# MercurialSDR_FPGA_P_P.net
KiCad netlist of a schematic drawn in Altium Designer
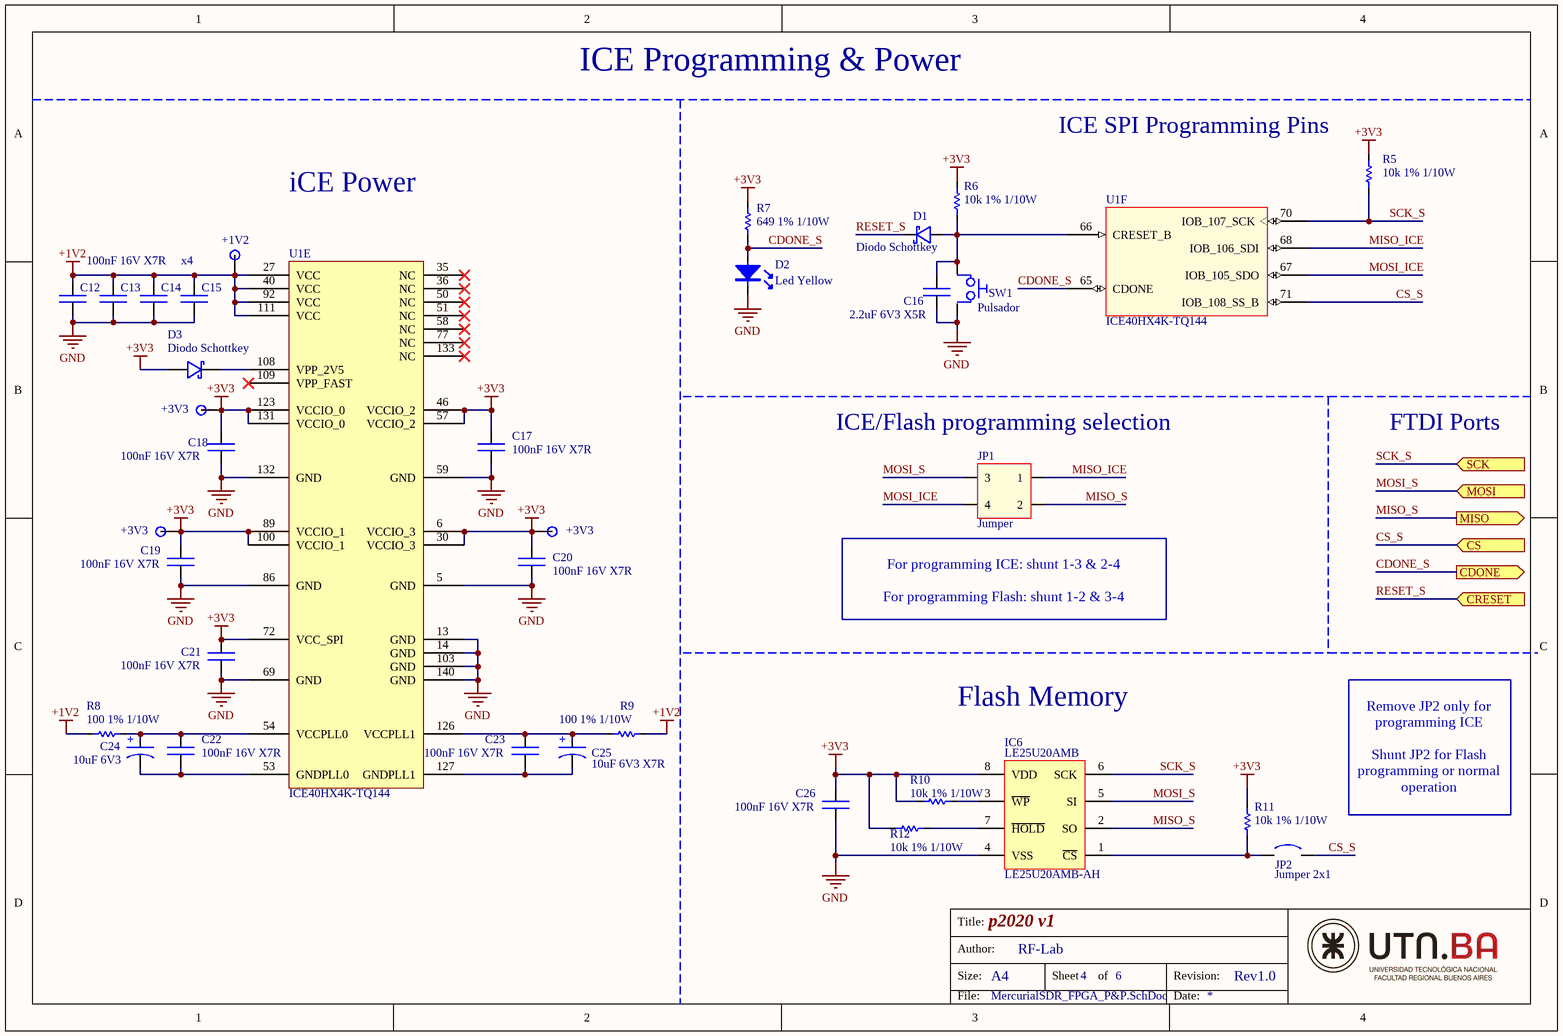
[diagram p0: MercurialSDR_FPGA_P&P.SchDoc]

(export (version "E")
  (design (tool "Eeschema 10.0.6"))
  (components
    (comp (ref "C12")
      (value "100nF 16V X7R - CL10B104KO8NNNC")
      (footprint "CAP_0603")
      (description "Capacitor no polarizado")
      (libsource (lib "MercurialSDR") (part "Cap"))
    )
    (comp (ref "C13")
      (value "100nF 16V X7R - CL10B104KO8NNNC")
      (footprint "CAP_0603")
      (description "Capacitor no polarizado")
      (fields (field (name "PART NUMBER") "CL10B104KO8NNNC"))
      (libsource (lib "MercurialSDR") (part "Cap"))
    )
    (comp (ref "C14")
      (value "100nF 16V X7R - CL10B104KO8NNNC")
      (footprint "CAP_0603")
      (description "Capacitor no polarizado")
      (fields (field (name "PART NUMBER") "CL10B104KO8NNNC"))
      (libsource (lib "MercurialSDR") (part "Cap"))
    )
    (comp (ref "C15")
      (value "100nF 16V X7R")
      (footprint "CAP_0603")
      (description "Capacitor no polarizado")
      (fields (field (name "Comment") "100nF 16V X7R - CL10B104KO8NNNC"))
      (libsource (lib "MercurialSDR") (part "Cap"))
    )
    (comp (ref "C16")
      (value "2.2uF 6V3 X5R")
      (footprint "CAP_0603")
      (description "Capacitor no polarizado")
      (fields (field (name "Comment") "2.2uF 6V3 X5R - CL10A225KQ8NNNC"))
      (libsource (lib "MercurialSDR") (part "Cap"))
    )
    (comp (ref "C17")
      (value "100nF 16V X7R")
      (footprint "CAP_0603")
      (description "Capacitor no polarizado")
      (fields (field (name "Comment") "100nF 16V X7R - CL10B104KO8NNNC"))
      (libsource (lib "MercurialSDR") (part "Cap"))
    )
    (comp (ref "C18")
      (value "100nF 16V X7R")
      (footprint "CAP_0603")
      (description "Capacitor no polarizado")
      (fields (field (name "Comment") "100nF 16V X7R - CL10B104KO8NNNC"))
      (libsource (lib "MercurialSDR") (part "Cap"))
    )
    (comp (ref "C19")
      (value "100nF 16V X7R")
      (footprint "CAP_0603")
      (description "Capacitor no polarizado")
      (fields (field (name "Comment") "100nF 16V X7R - CL10B104KO8NNNC"))
      (libsource (lib "MercurialSDR") (part "Cap"))
    )
    (comp (ref "C20")
      (value "100nF 16V X7R")
      (footprint "CAP_0603")
      (description "Capacitor no polarizado")
      (fields (field (name "Comment") "100nF 16V X7R - CL10B104KO8NNNC"))
      (libsource (lib "MercurialSDR") (part "Cap"))
    )
    (comp (ref "C21")
      (value "100nF 16V X7R")
      (footprint "CAP_0603")
      (description "Capacitor no polarizado")
      (fields (field (name "Comment") "100nF 16V X7R - CL10B104KO8NNNC"))
      (libsource (lib "MercurialSDR") (part "Cap"))
    )
    (comp (ref "C22")
      (value "100nF 16V X7R")
      (footprint "CAP_0603")
      (description "Capacitor no polarizado")
      (fields (field (name "Comment") "100nF 16V X7R - CL10B104KO8NNNC"))
      (libsource (lib "MercurialSDR") (part "Cap"))
    )
    (comp (ref "C23")
      (value "100nF 16V X7R")
      (footprint "CAP_0603")
      (description "Capacitor no polarizado")
      (fields (field (name "Comment") "100nF 16V X7R - CL10B104KO8NNNC"))
      (libsource (lib "MercurialSDR") (part "Cap"))
    )
    (comp (ref "C24")
      (value "10uF 6V3")
      (footprint "CAP_TANT_1206")
      (description "Capacitor polarizado")
      (fields (field (name "Comment") "10uF 6V3 - TAJA106K006RNJ"))
      (libsource (lib "MercurialSDR") (part "Cap Pol"))
    )
    (comp (ref "C25")
      (value "10uF 6V3 X7R")
      (footprint "CAP_TANT_1206")
      (description "Capacitor polarizado")
      (fields (field (name "Comment") "10uF 6V3 X7R- TAJA106K006RNJ"))
      (libsource (lib "MercurialSDR") (part "Cap Pol"))
    )
    (comp (ref "C26")
      (value "100nF 16V X7R")
      (footprint "CAP_0603")
      (description "Capacitor no polarizado")
      (fields (field (name "Comment") "100nF 16V X7R - CL10B104KO8NNNC"))
      (libsource (lib "MercurialSDR") (part "Cap"))
    )
    (comp (ref "D1")
      (value "Diodo Schottkey")
      (footprint "SOD-523")
      (fields (field (name "Comment") "RB521S30T1G"))
      (libsource (lib "MercurialSDR") (part "Diodo_Schottky"))
    )
    (comp (ref "D2")
      (value "Led Yellow")
      (footprint "LED_0603")
      (description "Led")
      (fields (field (name "Comment") "LTST-C190KSKT"))
      (libsource (lib "MercurialSDR") (part "Led"))
    )
    (comp (ref "D3")
      (value "Diodo Schottkey")
      (footprint "SOD-323")
      (fields (field (name "PART NUMBER") "NSR0530HT1G"))
      (libsource (lib "") (part "Diodo_Schottky_1"))
    )
    (comp (ref "IC6")
      (value "LE25U20AMB")
      (footprint "SOIC-8")
      (description "Flash Memmory SPI (256Kx8)")
      (fields (field (name "PART NUMBER") "LE25U20AMB-AH"))
      (libsource (lib "MercurialSDR") (part "LE25U20AMB"))
    )
    (comp (ref "JP1")
      (value "Jumper")
      (footprint "Jumper 2x2")
      (description "Jumper 2x2")
      (libsource (lib "MercurialSDR") (part "Jumper 2x2"))
    )
    (comp (ref "JP2")
      (value "Jumper 2x1")
      (footprint "Jumper 2x1")
      (description "Jumper")
      (libsource (lib "MercurialSDR") (part "Jumper"))
    )
    (comp (ref "R5")
      (value "10k 1% 1/10W")
      (footprint "RES_0603")
      (description "Resistor")
      (fields (field (name "Comment") "10k 1% 1/10W - CR0603-FX-1002EAS"))
      (libsource (lib "MercurialSDR") (part "Res"))
    )
    (comp (ref "R6")
      (value "10k 1% 1/10W")
      (footprint "RES_0603")
      (description "Resistor")
      (fields (field (name "Comment") "10k 1% 1/10W - CR0603-FX-1002EAS"))
      (libsource (lib "MercurialSDR") (part "Res"))
    )
    (comp (ref "R7")
      (value "649 1% 1/10W")
      (footprint "RES_0603")
      (description "Resistor")
      (fields (field (name "Comment") "649 1% 1/10W - RC0603FR-07649RL"))
      (libsource (lib "MercurialSDR") (part "Res"))
    )
    (comp (ref "R8")
      (value "100 1% 1/10W")
      (footprint "RES_0603")
      (description "Resistor")
      (fields (field (name "Comment") "100 1% 1/10W - CR0603-FX-1000ELF"))
      (libsource (lib "MercurialSDR") (part "Res"))
    )
    (comp (ref "R9")
      (value "100 1% 1/10W")
      (footprint "RES_0603")
      (description "Resistor")
      (fields (field (name "POWER") "1/10W") (field (name "PART NUMBER") "CR0603-FX-1000ELF"))
      (libsource (lib "MercurialSDR") (part "Res"))
    )
    (comp (ref "R10")
      (value "10k 1% 1/10W")
      (footprint "RES_0603")
      (description "Resistor")
      (fields (field (name "Comment") "10k 1% 1/10W - CR0603-FX-1002EAS"))
      (libsource (lib "MercurialSDR") (part "Res"))
    )
    (comp (ref "R11")
      (value "10k 1% 1/10W")
      (footprint "RES_0603")
      (description "Resistor")
      (fields (field (name "Comment") "10k 1% 1/10W - CR0603-FX-1002EAS"))
      (libsource (lib "MercurialSDR") (part "Res"))
    )
    (comp (ref "R12")
      (value "10k 1% 1/10W")
      (footprint "RES_0603")
      (description "Resistor")
      (fields (field (name "Comment") "10k 1% 1/10W - CR0603-FX-1002EAS"))
      (libsource (lib "MercurialSDR") (part "Res"))
    )
    (comp (ref "SW1")
      (value "Pulsador")
      (footprint "SWITCH_6X6mm")
      (fields (field (name "Comment") "PTS645SM43SMTR92 LFS"))
      (libsource (lib "MercurialSDR") (part "Pulsador"))
    )
    (comp (ref "TP2")
      (value "Test Point")
      (footprint "TP_TH")
      (fields (field (name "TP NAME") "+1V2"))
      (libsource (lib "MercurialSDR") (part "Test Point"))
    )
    (comp (ref "TP3")
      (value "Test Point")
      (footprint "TP_TH")
      (fields (field (name "TP NAME") "+3V3"))
      (libsource (lib "MercurialSDR") (part "Test Point"))
    )
    (comp (ref "TP4")
      (value "Test Point")
      (footprint "TP_TH")
      (fields (field (name "TP NAME") "+3V3"))
      (libsource (lib "MercurialSDR") (part "Test Point"))
    )
    (comp (ref "TP5")
      (value "Test Point")
      (footprint "TP_TH")
      (fields (field (name "TP NAME") "+3V3"))
      (libsource (lib "MercurialSDR") (part "Test Point"))
    )
    (comp (ref "U1")
      (value "ICE40HX4K-TQ144")
      (footprint "LATC-TQFP-144_L")
      (description "iCE40 HX4K Series FPGA Family")
      (fields (field (name "MANUFACTURER") "Lattice Semiconductor"))
      (libsource (lib "MercurialSDR") (part "ICE40HX4K-TQ144"))
    )
  )
  (nets
    (net (code "1") (name "+1V2") (class "Default")
      (node (ref "C12") (pin "1") (pinfunction "1_1") (pintype "passive"))
      (node (ref "C13") (pin "1") (pinfunction "1_1") (pintype "passive"))
      (node (ref "C14") (pin "1") (pinfunction "1_1") (pintype "passive"))
      (node (ref "C15") (pin "1") (pinfunction "1_1") (pintype "passive"))
      (node (ref "R8") (pin "2") (pinfunction "2_2") (pintype "passive"))
      (node (ref "R9") (pin "1") (pinfunction "1_1") (pintype "passive"))
      (node (ref "TP2") (pin "1") (pinfunction "TP?_1") (pintype "passive"))
      (node (ref "U1") (pin "111") (pinfunction "VCC_111") (pintype "power_in"))
      (node (ref "U1") (pin "27") (pinfunction "VCC_27") (pintype "power_in"))
      (node (ref "U1") (pin "40") (pinfunction "VCC_40") (pintype "power_in"))
      (node (ref "U1") (pin "92") (pinfunction "VCC_92") (pintype "power_in"))
    )
    (net (code "2") (name "+3V3") (class "Default")
      (node (ref "C17") (pin "2") (pinfunction "2_2") (pintype "passive"))
      (node (ref "C18") (pin "2") (pinfunction "2_2") (pintype "passive"))
      (node (ref "C19") (pin "2") (pinfunction "2_2") (pintype "passive"))
      (node (ref "C20") (pin "2") (pinfunction "2_2") (pintype "passive"))
      (node (ref "C21") (pin "2") (pinfunction "2_2") (pintype "passive"))
      (node (ref "C26") (pin "2") (pinfunction "2_2") (pintype "passive"))
      (node (ref "D3") (pin "1") (pinfunction "A_1") (pintype "passive"))
      (node (ref "IC6") (pin "8") (pinfunction "VDD_8") (pintype "passive"))
      (node (ref "R10") (pin "1") (pinfunction "1_1") (pintype "passive"))
      (node (ref "R11") (pin "2") (pinfunction "2_2") (pintype "passive"))
      (node (ref "R12") (pin "1") (pinfunction "1_1") (pintype "passive"))
      (node (ref "R5") (pin "1") (pinfunction "1_1") (pintype "passive"))
      (node (ref "R6") (pin "1") (pinfunction "1_1") (pintype "passive"))
      (node (ref "R7") (pin "1") (pinfunction "1_1") (pintype "passive"))
      (node (ref "TP3") (pin "1") (pinfunction "TP?_1") (pintype "passive"))
      (node (ref "TP4") (pin "1") (pinfunction "TP?_1") (pintype "passive"))
      (node (ref "TP5") (pin "1") (pinfunction "TP?_1") (pintype "passive"))
      (node (ref "U1") (pin "100") (pinfunction "VCCIO_1_100") (pintype "power_in"))
      (node (ref "U1") (pin "123") (pinfunction "VCCIO_0_123") (pintype "power_in"))
      (node (ref "U1") (pin "131") (pinfunction "VCCIO_0_131") (pintype "power_in"))
      (node (ref "U1") (pin "30") (pinfunction "VCCIO_3_30") (pintype "power_in"))
      (node (ref "U1") (pin "46") (pinfunction "VCCIO_2_46") (pintype "power_in"))
      (node (ref "U1") (pin "57") (pinfunction "VCCIO_2_57") (pintype "power_in"))
      (node (ref "U1") (pin "6") (pinfunction "VCCIO_3_6") (pintype "power_in"))
      (node (ref "U1") (pin "72") (pinfunction "VCC_SPI_72") (pintype "power_in"))
      (node (ref "U1") (pin "89") (pinfunction "VCCIO_1_89") (pintype "power_in"))
    )
    (net (code "3") (name "/CDONE_S") (class "Default")
      (node (ref "D2") (pin "1") (pinfunction "A_1") (pintype "passive"))
      (node (ref "R7") (pin "2") (pinfunction "2_2") (pintype "passive"))
      (node (ref "U1") (pin "65") (pinfunction "CDONE_65") (pintype "bidirectional"))
    )
    (net (code "4") (name "/CS_S") (class "Default")
      (node (ref "JP2") (pin "2") (pinfunction "2_2") (pintype "passive"))
      (node (ref "U1") (pin "71") (pinfunction "IOB_108_SS_B_71") (pintype "bidirectional"))
    )
    (net (code "5") (name "/MISO_ICE") (class "Default")
      (node (ref "JP1") (pin "1") (pinfunction "1_1") (pintype "passive"))
      (node (ref "U1") (pin "68") (pinfunction "IOB_106_SDI_68") (pintype "bidirectional"))
    )
    (net (code "6") (name "/MISO_S") (class "Default")
      (node (ref "IC6") (pin "2") (pinfunction "SO_2") (pintype "passive"))
      (node (ref "JP1") (pin "2") (pinfunction "2_2") (pintype "passive"))
    )
    (net (code "7") (name "/MOSI_ICE") (class "Default")
      (node (ref "JP1") (pin "4") (pinfunction "4_4") (pintype "passive"))
      (node (ref "U1") (pin "67") (pinfunction "IOB_105_SDO_67") (pintype "bidirectional"))
    )
    (net (code "8") (name "/MOSI_S") (class "Default")
      (node (ref "IC6") (pin "5") (pinfunction "SI_5") (pintype "passive"))
      (node (ref "JP1") (pin "3") (pinfunction "3_3") (pintype "passive"))
    )
    (net (code "9") (name "/RESET_S") (class "Default")
      (node (ref "D1") (pin "2") (pinfunction "K_2") (pintype "passive"))
    )
    (net (code "10") (name "/SCK_S") (class "Default")
      (node (ref "IC6") (pin "6") (pinfunction "SCK_6") (pintype "passive"))
      (node (ref "R5") (pin "2") (pinfunction "2_2") (pintype "passive"))
      (node (ref "U1") (pin "70") (pinfunction "IOB_107_SCK_70") (pintype "bidirectional"))
    )
    (net (code "11") (name "GND") (class "Default")
      (node (ref "C12") (pin "2") (pinfunction "2_2") (pintype "passive"))
      (node (ref "C13") (pin "2") (pinfunction "2_2") (pintype "passive"))
      (node (ref "C14") (pin "2") (pinfunction "2_2") (pintype "passive"))
      (node (ref "C15") (pin "2") (pinfunction "2_2") (pintype "passive"))
      (node (ref "C16") (pin "2") (pinfunction "2_2") (pintype "passive"))
      (node (ref "C17") (pin "1") (pinfunction "1_1") (pintype "passive"))
      (node (ref "C18") (pin "1") (pinfunction "1_1") (pintype "passive"))
      (node (ref "C19") (pin "1") (pinfunction "1_1") (pintype "passive"))
      (node (ref "C20") (pin "1") (pinfunction "1_1") (pintype "passive"))
      (node (ref "C21") (pin "1") (pinfunction "1_1") (pintype "passive"))
      (node (ref "C26") (pin "1") (pinfunction "1_1") (pintype "passive"))
      (node (ref "D2") (pin "2") (pinfunction "K_2") (pintype "passive"))
      (node (ref "IC6") (pin "4") (pinfunction "VSS_4") (pintype "passive"))
      (node (ref "SW1") (pin "4") (pinfunction "4_4") (pintype "passive"))
      (node (ref "U1") (pin "103") (pinfunction "GND_103") (pintype "power_in"))
      (node (ref "U1") (pin "13") (pinfunction "GND_13") (pintype "power_in"))
      (node (ref "U1") (pin "132") (pinfunction "GND_132") (pintype "power_in"))
      (node (ref "U1") (pin "14") (pinfunction "GND_14") (pintype "power_in"))
      (node (ref "U1") (pin "140") (pinfunction "GND_140") (pintype "power_in"))
      (node (ref "U1") (pin "5") (pinfunction "GND_5") (pintype "power_in"))
      (node (ref "U1") (pin "59") (pinfunction "GND_59") (pintype "power_in"))
      (node (ref "U1") (pin "69") (pinfunction "GND_69") (pintype "power_in"))
      (node (ref "U1") (pin "86") (pinfunction "GND_86") (pintype "power_in"))
    )
    (net (code "12") (name "Net-(D1-A)") (class "Default")
      (node (ref "C16") (pin "1") (pinfunction "1_1") (pintype "passive"))
      (node (ref "D1") (pin "1") (pinfunction "A_1") (pintype "passive"))
      (node (ref "R6") (pin "2") (pinfunction "2_2") (pintype "passive"))
      (node (ref "SW1") (pin "1") (pinfunction "1_1") (pintype "passive"))
      (node (ref "U1") (pin "66") (pinfunction "CRESET_B_66") (pintype "input"))
    )
    (net (code "13") (name "Net-(D3-K)") (class "Default")
      (node (ref "D3") (pin "2") (pinfunction "K_2") (pintype "passive"))
      (node (ref "U1") (pin "108") (pinfunction "VPP_2V5_108") (pintype "power_in"))
    )
    (net (code "14") (name "Net-(IC6-~{CS})") (class "Default")
      (node (ref "IC6") (pin "1") (pinfunction "~{CS}_1") (pintype "passive"))
      (node (ref "JP2") (pin "1") (pinfunction "1_1") (pintype "passive"))
      (node (ref "R11") (pin "1") (pinfunction "1_1") (pintype "passive"))
    )
    (net (code "15") (name "Net-(IC6-~{HOLD})") (class "Default")
      (node (ref "IC6") (pin "7") (pinfunction "~{HOLD}_7") (pintype "passive"))
      (node (ref "R12") (pin "2") (pinfunction "2_2") (pintype "passive"))
    )
    (net (code "16") (name "Net-(IC6-~{WP})") (class "Default")
      (node (ref "IC6") (pin "3") (pinfunction "~{WP}_3") (pintype "passive"))
      (node (ref "R10") (pin "2") (pinfunction "2_2") (pintype "passive"))
    )
    (net (code "17") (name "Net-(U1E-GNDPLL0)") (class "Default")
      (node (ref "C22") (pin "2") (pinfunction "2_2") (pintype "passive"))
      (node (ref "C24") (pin "2") (pinfunction "2_2") (pintype "passive"))
      (node (ref "U1") (pin "53") (pinfunction "GNDPLL0_53") (pintype "power_in"))
    )
    (net (code "18") (name "Net-(U1E-GNDPLL1)") (class "Default")
      (node (ref "C23") (pin "2") (pinfunction "2_2") (pintype "passive"))
      (node (ref "C25") (pin "2") (pinfunction "2_2") (pintype "passive"))
      (node (ref "U1") (pin "127") (pinfunction "GNDPLL1_127") (pintype "power_in"))
    )
    (net (code "19") (name "Net-(U1E-VCCPLL0)") (class "Default")
      (node (ref "C22") (pin "1") (pinfunction "1_1") (pintype "passive"))
      (node (ref "C24") (pin "1") (pinfunction "1_1") (pintype "passive"))
      (node (ref "R8") (pin "1") (pinfunction "1_1") (pintype "passive"))
      (node (ref "U1") (pin "54") (pinfunction "VCCPLL0_54") (pintype "power_in"))
    )
    (net (code "20") (name "Net-(U1E-VCCPLL1)") (class "Default")
      (node (ref "C23") (pin "1") (pinfunction "1_1") (pintype "passive"))
      (node (ref "C25") (pin "1") (pinfunction "1_1") (pintype "passive"))
      (node (ref "R9") (pin "2") (pinfunction "2_2") (pintype "passive"))
      (node (ref "U1") (pin "126") (pinfunction "VCCPLL1_126") (pintype "power_in"))
    )
    (net (code "21") (name "unconnected-(SW1-Pad2)") (class "Default")
      (node (ref "SW1") (pin "2") (pinfunction "2_2") (pintype "passive"))
    )
    (net (code "22") (name "unconnected-(SW1-Pad3)") (class "Default")
      (node (ref "SW1") (pin "3") (pinfunction "3_3") (pintype "passive"))
    )
    (net (code "23") (name "unconnected-(U1E-NC-Pad35)") (class "Default")
      (node (ref "U1") (pin "35") (pinfunction "NC_35") (pintype "passive+no_connect"))
    )
    (net (code "24") (name "unconnected-(U1E-NC-Pad36)") (class "Default")
      (node (ref "U1") (pin "36") (pinfunction "NC_36") (pintype "passive+no_connect"))
    )
    (net (code "25") (name "unconnected-(U1E-NC-Pad50)") (class "Default")
      (node (ref "U1") (pin "50") (pinfunction "NC_50") (pintype "passive+no_connect"))
    )
    (net (code "26") (name "unconnected-(U1E-NC-Pad51)") (class "Default")
      (node (ref "U1") (pin "51") (pinfunction "NC_51") (pintype "passive+no_connect"))
    )
    (net (code "27") (name "unconnected-(U1E-NC-Pad58)") (class "Default")
      (node (ref "U1") (pin "58") (pinfunction "NC_58") (pintype "passive+no_connect"))
    )
    (net (code "28") (name "unconnected-(U1E-NC-Pad77)") (class "Default")
      (node (ref "U1") (pin "77") (pinfunction "NC_77") (pintype "passive+no_connect"))
    )
    (net (code "29") (name "unconnected-(U1E-NC-Pad133)") (class "Default")
      (node (ref "U1") (pin "133") (pinfunction "NC_133") (pintype "passive+no_connect"))
    )
    (net (code "30") (name "unconnected-(U1E-VPP_FAST-Pad109)") (class "Default")
      (node (ref "U1") (pin "109") (pinfunction "VPP_FAST_109") (pintype "power_in+no_connect"))
    )
  )
)
